# IO.net
KiCad netlist of a schematic drawn in Altium Designer
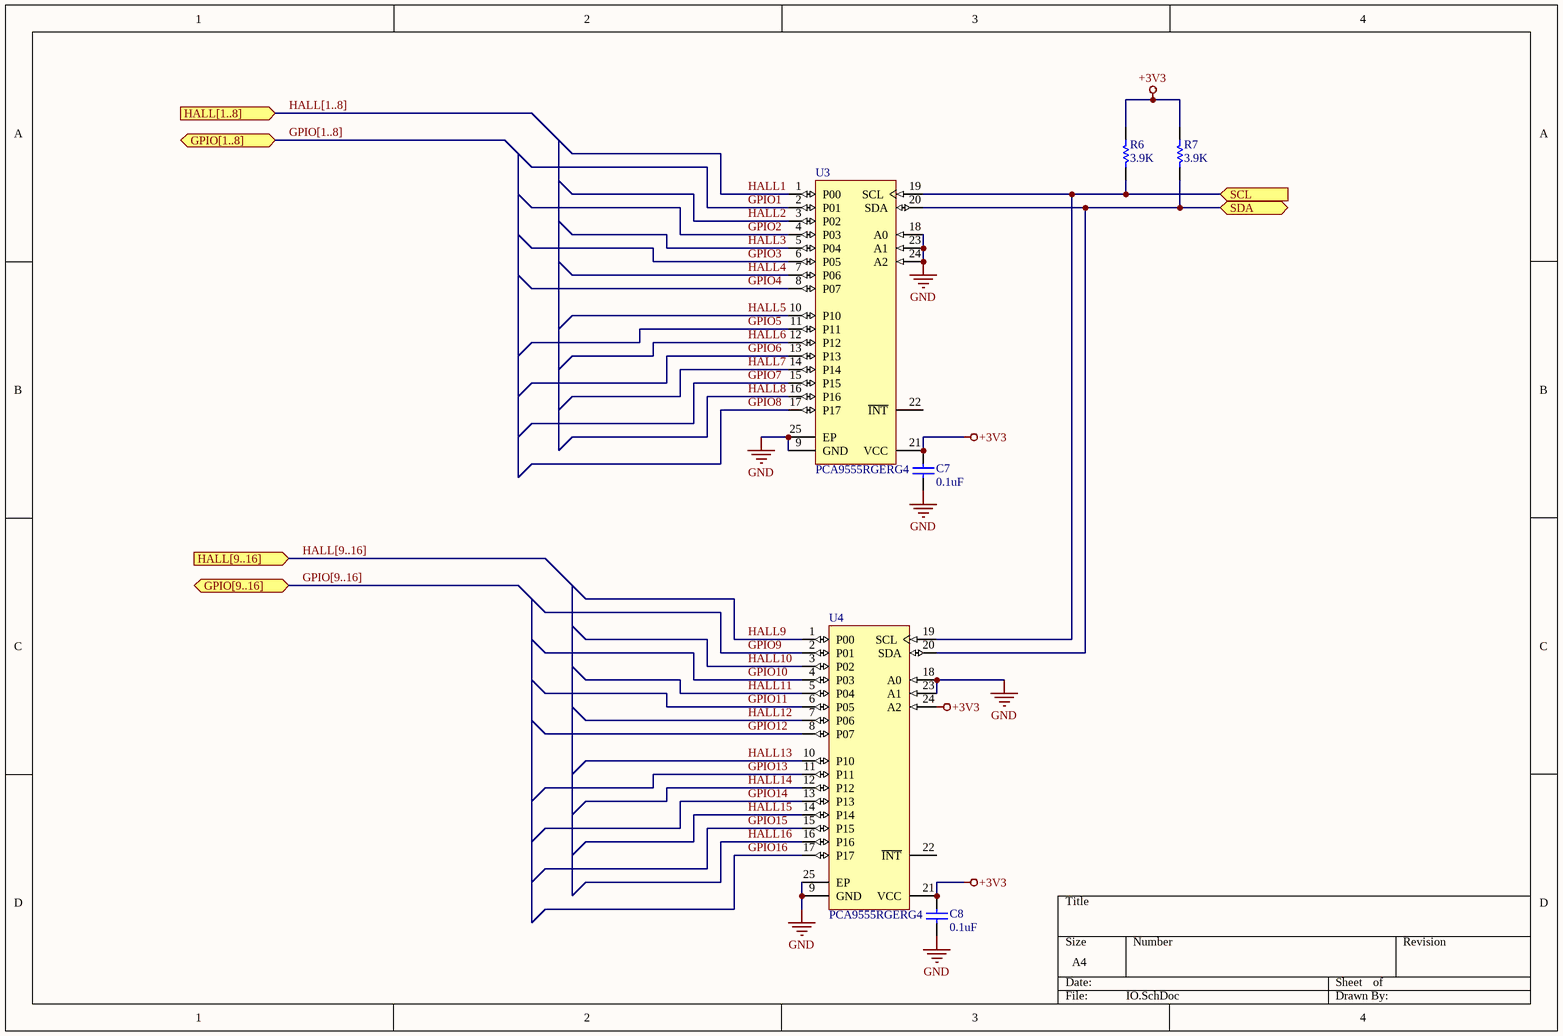
[diagram p0: IO.SchDoc]

(export (version "E")
  (design (tool "Eeschema 10.0.6"))
  (components
    (comp (ref "C7")
      (value "0.1uF")
      (footprint "CAPC1608X87X35NL15T15")
      (fields (field (name "PART NUMBER") "C0603X104K5RACTU") (field (name "MANUFACTURER") "Kemet"))
      (libsource (lib "Altium Content Vault") (part "CAP"))
    )
    (comp (ref "C8")
      (value "0.1uF")
      (footprint "CAPC1608X87X35NL15T15")
      (fields (field (name "PART NUMBER") "C0603X104K5RACTU") (field (name "MANUFACTURER") "Kemet"))
      (libsource (lib "Altium Content Vault") (part "CAP"))
    )
    (comp (ref "R6")
      (value "3.9K")
      (footprint "RESC1608X55X30ML15T15")
      (fields (field (name "PART NUMBER") "ERJ-3EKF1001V") (field (name "MANUFACTURER") "Panasonic"))
      (libsource (lib "Altium Content Vault") (part "RES"))
    )
    (comp (ref "R7")
      (value "3.9K")
      (footprint "RESC1608X55X30ML15T15")
      (fields (field (name "PART NUMBER") "ERJ-3EKF1001V") (field (name "MANUFACTURER") "Panasonic"))
      (libsource (lib "Altium Content Vault") (part "RES"))
    )
    (comp (ref "U3")
      (value "PCA9555RGERG4")
      (footprint "RGE24-2100X2100TP")
      (fields (field (name "MANUFACTURER") "Texas Instruments"))
      (libsource (lib "Altium Content Vault") (part "TI-PCA9555-VQFN_RGE-24"))
    )
    (comp (ref "U4")
      (value "PCA9555RGERG4")
      (footprint "RGE24-2100X2100TP")
      (fields (field (name "MANUFACTURER") "Texas Instruments"))
      (libsource (lib "Altium Content Vault") (part "TI-PCA9555-VQFN_RGE-24"))
    )
  )
  (nets
    (net (code "1") (name "+3V3") (class "Default")
      (node (ref "C7") (pin "1") (pinfunction "1_1") (pintype "passive"))
      (node (ref "C8") (pin "1") (pinfunction "1_1") (pintype "passive"))
      (node (ref "R6") (pin "2") (pinfunction "2_2") (pintype "passive"))
      (node (ref "R7") (pin "2") (pinfunction "2_2") (pintype "passive"))
      (node (ref "U3") (pin "21") (pinfunction "VCC_21") (pintype "power_in"))
      (node (ref "U4") (pin "21") (pinfunction "VCC_21") (pintype "power_in"))
      (node (ref "U4") (pin "24") (pinfunction "A2_24") (pintype "input"))
    )
    (net (code "2") (name "/GPIO1") (class "Default")
      (node (ref "U3") (pin "2") (pinfunction "P01_2") (pintype "bidirectional"))
    )
    (net (code "3") (name "/GPIO2") (class "Default")
      (node (ref "U3") (pin "4") (pinfunction "P03_4") (pintype "bidirectional"))
    )
    (net (code "4") (name "/GPIO3") (class "Default")
      (node (ref "U3") (pin "6") (pinfunction "P05_6") (pintype "bidirectional"))
    )
    (net (code "5") (name "/GPIO4") (class "Default")
      (node (ref "U3") (pin "8") (pinfunction "P07_8") (pintype "bidirectional"))
    )
    (net (code "6") (name "/GPIO5") (class "Default")
      (node (ref "U3") (pin "11") (pinfunction "P11_11") (pintype "bidirectional"))
    )
    (net (code "7") (name "/GPIO6") (class "Default")
      (node (ref "U3") (pin "13") (pinfunction "P13_13") (pintype "bidirectional"))
    )
    (net (code "8") (name "/GPIO7") (class "Default")
      (node (ref "U3") (pin "15") (pinfunction "P15_15") (pintype "bidirectional"))
    )
    (net (code "9") (name "/GPIO8") (class "Default")
      (node (ref "U3") (pin "17") (pinfunction "P17_17") (pintype "bidirectional"))
    )
    (net (code "10") (name "/GPIO9") (class "Default")
      (node (ref "U4") (pin "2") (pinfunction "P01_2") (pintype "bidirectional"))
    )
    (net (code "11") (name "/GPIO10") (class "Default")
      (node (ref "U4") (pin "4") (pinfunction "P03_4") (pintype "bidirectional"))
    )
    (net (code "12") (name "/GPIO11") (class "Default")
      (node (ref "U4") (pin "6") (pinfunction "P05_6") (pintype "bidirectional"))
    )
    (net (code "13") (name "/GPIO12") (class "Default")
      (node (ref "U4") (pin "8") (pinfunction "P07_8") (pintype "bidirectional"))
    )
    (net (code "14") (name "/GPIO13") (class "Default")
      (node (ref "U4") (pin "11") (pinfunction "P11_11") (pintype "bidirectional"))
    )
    (net (code "15") (name "/GPIO14") (class "Default")
      (node (ref "U4") (pin "13") (pinfunction "P13_13") (pintype "bidirectional"))
    )
    (net (code "16") (name "/GPIO15") (class "Default")
      (node (ref "U4") (pin "15") (pinfunction "P15_15") (pintype "bidirectional"))
    )
    (net (code "17") (name "/GPIO16") (class "Default")
      (node (ref "U4") (pin "17") (pinfunction "P17_17") (pintype "bidirectional"))
    )
    (net (code "20") (name "/HALL1") (class "Default")
      (node (ref "U3") (pin "1") (pinfunction "P00_1") (pintype "bidirectional"))
    )
    (net (code "21") (name "/HALL2") (class "Default")
      (node (ref "U3") (pin "3") (pinfunction "P02_3") (pintype "bidirectional"))
    )
    (net (code "22") (name "/HALL3") (class "Default")
      (node (ref "U3") (pin "5") (pinfunction "P04_5") (pintype "bidirectional"))
    )
    (net (code "23") (name "/HALL4") (class "Default")
      (node (ref "U3") (pin "7") (pinfunction "P06_7") (pintype "bidirectional"))
    )
    (net (code "24") (name "/HALL5") (class "Default")
      (node (ref "U3") (pin "10") (pinfunction "P10_10") (pintype "bidirectional"))
    )
    (net (code "25") (name "/HALL6") (class "Default")
      (node (ref "U3") (pin "12") (pinfunction "P12_12") (pintype "bidirectional"))
    )
    (net (code "26") (name "/HALL7") (class "Default")
      (node (ref "U3") (pin "14") (pinfunction "P14_14") (pintype "bidirectional"))
    )
    (net (code "27") (name "/HALL8") (class "Default")
      (node (ref "U3") (pin "16") (pinfunction "P16_16") (pintype "bidirectional"))
    )
    (net (code "28") (name "/HALL9") (class "Default")
      (node (ref "U4") (pin "1") (pinfunction "P00_1") (pintype "bidirectional"))
    )
    (net (code "29") (name "/HALL10") (class "Default")
      (node (ref "U4") (pin "3") (pinfunction "P02_3") (pintype "bidirectional"))
    )
    (net (code "30") (name "/HALL11") (class "Default")
      (node (ref "U4") (pin "5") (pinfunction "P04_5") (pintype "bidirectional"))
    )
    (net (code "31") (name "/HALL12") (class "Default")
      (node (ref "U4") (pin "7") (pinfunction "P06_7") (pintype "bidirectional"))
    )
    (net (code "32") (name "/HALL13") (class "Default")
      (node (ref "U4") (pin "10") (pinfunction "P10_10") (pintype "bidirectional"))
    )
    (net (code "33") (name "/HALL14") (class "Default")
      (node (ref "U4") (pin "12") (pinfunction "P12_12") (pintype "bidirectional"))
    )
    (net (code "34") (name "/HALL15") (class "Default")
      (node (ref "U4") (pin "14") (pinfunction "P14_14") (pintype "bidirectional"))
    )
    (net (code "35") (name "/HALL16") (class "Default")
      (node (ref "U4") (pin "16") (pinfunction "P16_16") (pintype "bidirectional"))
    )
    (net (code "38") (name "/SCL") (class "Default")
      (node (ref "R6") (pin "1") (pinfunction "1_1") (pintype "passive"))
      (node (ref "U3") (pin "19") (pinfunction "SCL_19") (pintype "input"))
      (node (ref "U4") (pin "19") (pinfunction "SCL_19") (pintype "input"))
    )
    (net (code "39") (name "/SDA") (class "Default")
      (node (ref "R7") (pin "1") (pinfunction "1_1") (pintype "passive"))
      (node (ref "U3") (pin "20") (pinfunction "SDA_20") (pintype "bidirectional"))
      (node (ref "U4") (pin "20") (pinfunction "SDA_20") (pintype "bidirectional"))
    )
    (net (code "40") (name "GND") (class "Default")
      (node (ref "C7") (pin "2") (pinfunction "2_2") (pintype "passive"))
      (node (ref "C8") (pin "2") (pinfunction "2_2") (pintype "passive"))
      (node (ref "U3") (pin "18") (pinfunction "A0_18") (pintype "input"))
      (node (ref "U3") (pin "23") (pinfunction "A1_23") (pintype "input"))
      (node (ref "U3") (pin "24") (pinfunction "A2_24") (pintype "input"))
      (node (ref "U3") (pin "25") (pinfunction "EP_25") (pintype "passive"))
      (node (ref "U3") (pin "9") (pinfunction "GND_9") (pintype "power_in"))
      (node (ref "U4") (pin "18") (pinfunction "A0_18") (pintype "input"))
      (node (ref "U4") (pin "23") (pinfunction "A1_23") (pintype "input"))
      (node (ref "U4") (pin "25") (pinfunction "EP_25") (pintype "passive"))
      (node (ref "U4") (pin "9") (pinfunction "GND_9") (pintype "power_in"))
    )
    (net (code "41") (name "unconnected-(U3-~{INT}-Pad22)") (class "Default")
      (node (ref "U3") (pin "22") (pinfunction "~{INT}_22") (pintype "open_collector"))
    )
    (net (code "42") (name "unconnected-(U4-~{INT}-Pad22)") (class "Default")
      (node (ref "U4") (pin "22") (pinfunction "~{INT}_22") (pintype "open_collector"))
    )
  )
)
